# Beetech_Metro_Shield_1_2.net
KiCad netlist of a schematic drawn in Altium Designer
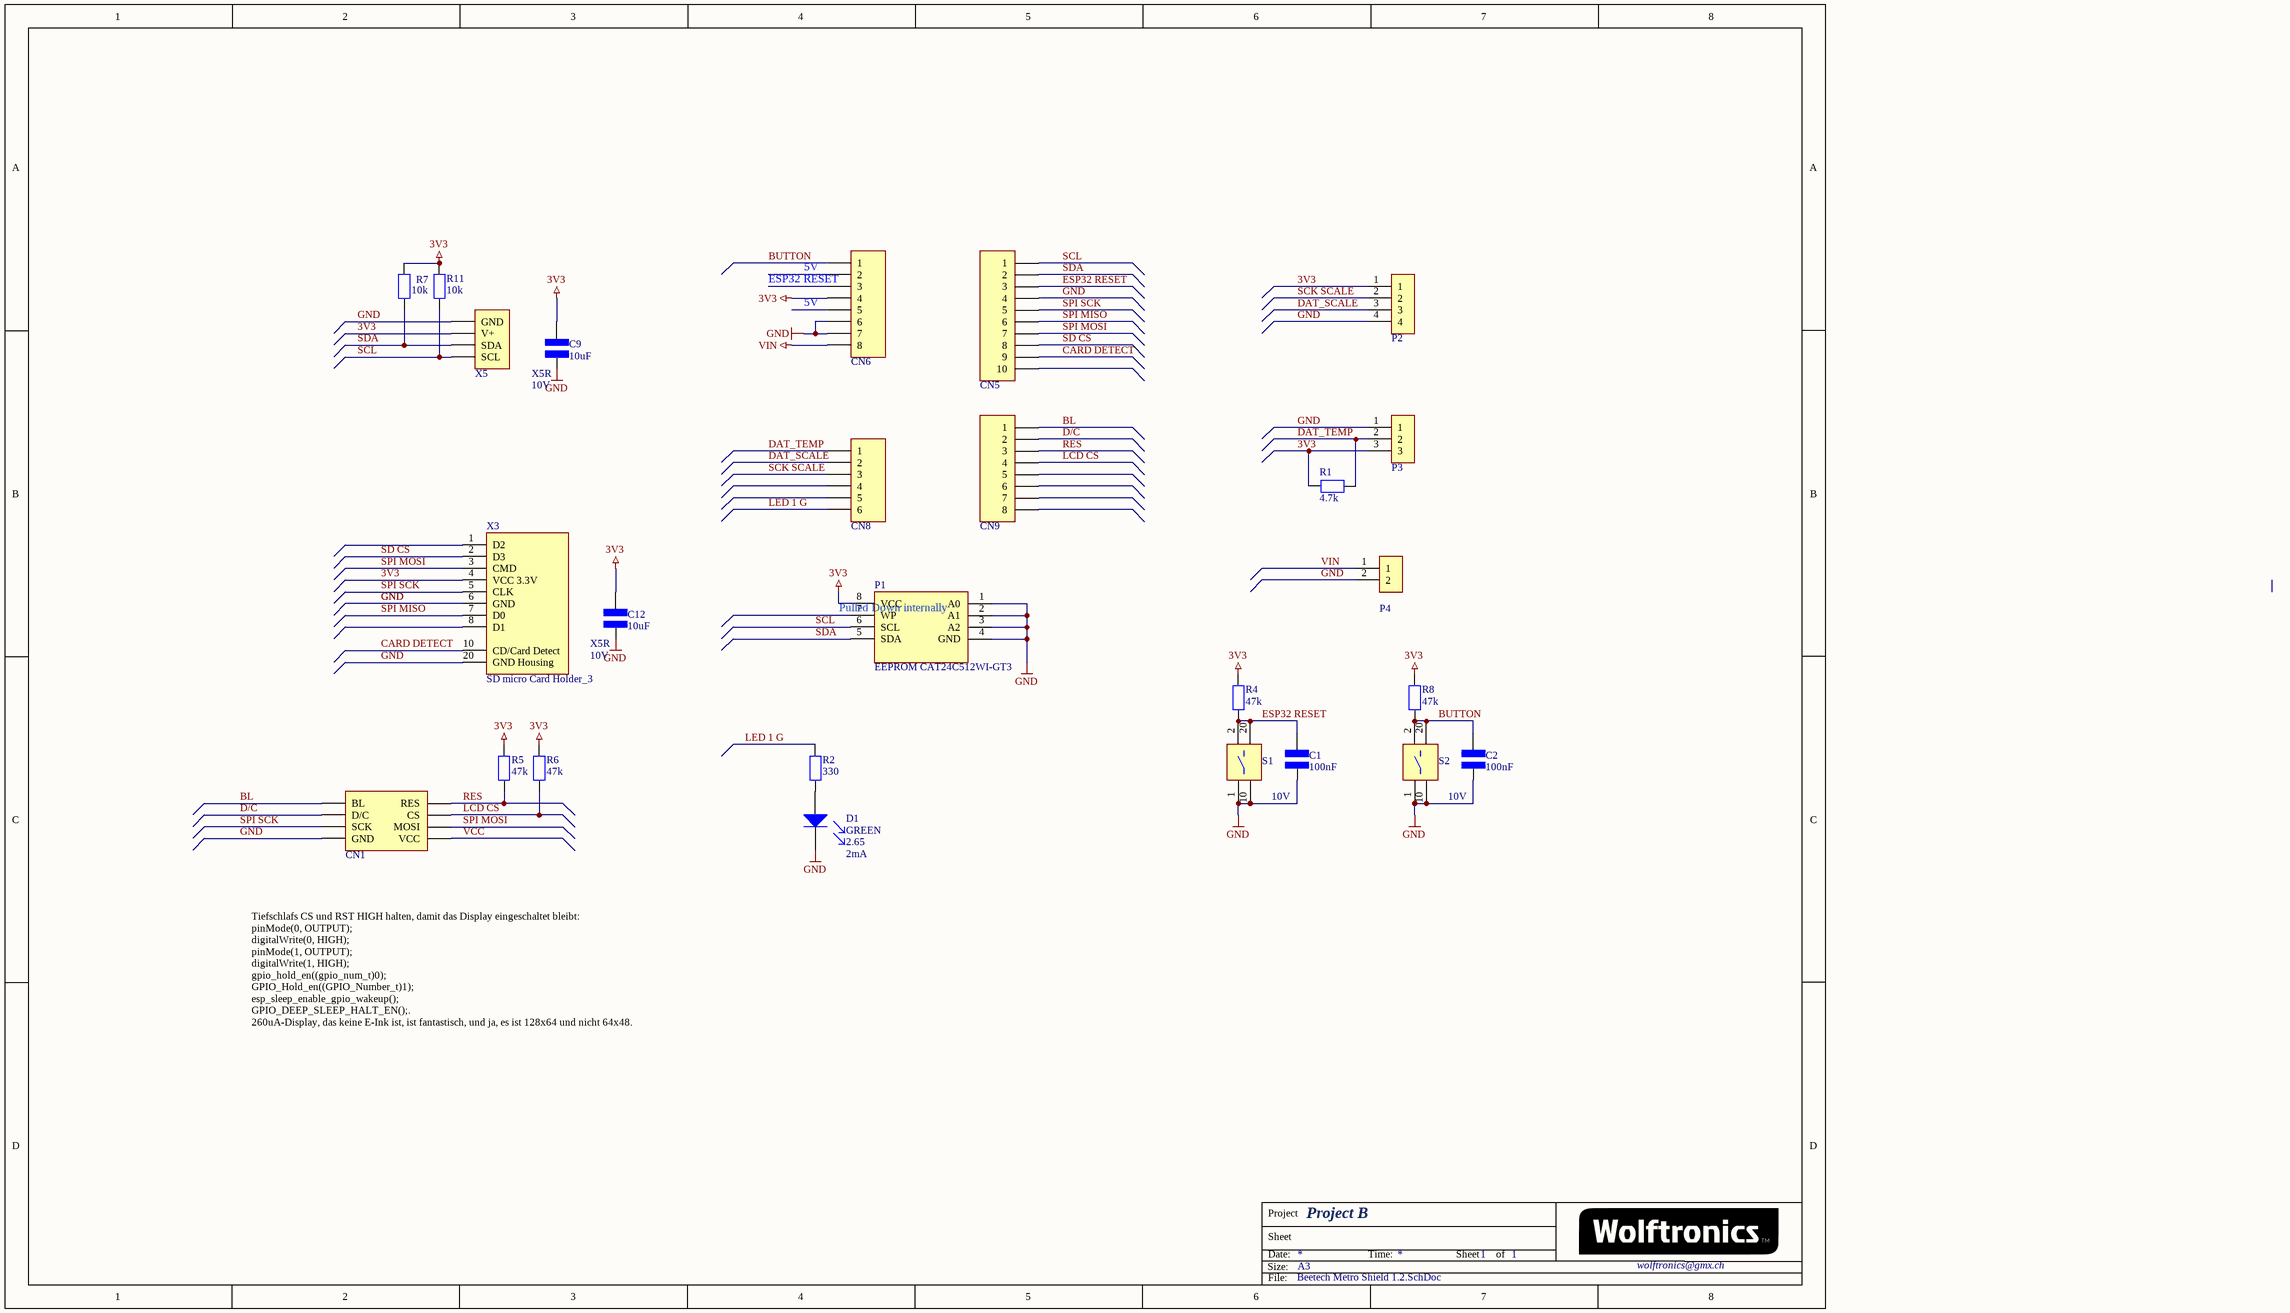
[diagram p0: Beetech Metro Shield 1.2.SchDoc]

(export (version "E")
  (design (tool "Eeschema 10.0.6"))
  (components
    (comp (ref "C1")
      (value "100nF")
      (footprint "CAP 0603 - OUTLINE")
      (description "C CERAMIC SMD")
      (fields (field (name "UMAX") "10V") (field (name "Comment") "100nF 0603"))
      (libsource (lib "Library CAP") (part "100nF 0603"))
    )
    (comp (ref "C2")
      (value "100nF")
      (footprint "CAP 0603 - OUTLINE")
      (description "C CERAMIC SMD")
      (fields (field (name "UMAX") "10V") (field (name "Comment") "100nF 0603"))
      (libsource (lib "Library CAP") (part "100nF 0603"))
    )
    (comp (ref "C9")
      (value "10uF")
      (footprint "CAP 0603 - OUTLINE")
      (description "C CERAMIC SMD")
      (fields
        (field (name "UMAX") "10V")
        (field (name "DIELEKTRIKUM") "X5R")
        (field (name "Comment") "10uF 0603")
      )
      (libsource (lib "Library CAP") (part "10uF 0603"))
    )
    (comp (ref "C12")
      (value "10uF")
      (footprint "CAP 0603 - OUTLINE")
      (description "C CERAMIC SMD")
      (fields
        (field (name "UMAX") "10V")
        (field (name "DIELEKTRIKUM") "X5R")
        (field (name "Comment") "10uF 0603")
      )
      (libsource (lib "Library CAP") (part "10uF 0603"))
    )
    (comp (ref "CN1")
      (value "LCD 1.37 Zoll Matrix")
      (footprint "LCD 1.37 Zoll Matrix LCD-Modul SPI-Schnittstelle Treiber AiP31567 - ST7567")
      (description "1,37 Zoll 1,37 Zoll Matrix LCD-Modul SPI-Schnittstelle AiP31567 Treiber Gleiche wie ST7567")
      (libsource (lib "Library Scematic") (part "LCD 1.37 Zoll Matrix"))
    )
    (comp (ref "CN5")
      (value "10-Pin Stiftleiste 10x1 2.54 Low Profile")
      (footprint "10PIN - III")
      (description "Low Profile 10-Pin Stiftleiste 10x1 2.54 Low Profile")
      (libsource (lib "Library Scematic") (part "10-Pin Stiftleiste 10x1 2.54 Low Profile"))
    )
    (comp (ref "CN6")
      (value "8-Pin Stiftleiste 8x1 2.54 Low Profile")
      (footprint "8 PIN - Stiftleiste")
      (description "Low Profile 8-Pin Stiftleiste 8x1 2.54")
      (libsource (lib "Library Scematic") (part "8-Pin Stiftleiste 8x1 2.54 Low Profile"))
    )
    (comp (ref "CN8")
      (value "6-PiN")
      (footprint "6PIN")
      (description "6-Pin")
      (fields (field (name "PUBLISHER") "Altium Limited"))
      (libsource (lib "Library Scematic") (part "6-PiN"))
    )
    (comp (ref "CN9")
      (value "8-Pin Stiftleiste 8x1 2.54 Low Profile")
      (footprint "8 PIN - Stiftleiste")
      (description "Low Profile 8-Pin Stiftleiste 8x1 2.54")
      (libsource (lib "") (part "8-Pin Stiftleiste 8x1 2.54 Low Profile_1"))
    )
    (comp (ref "D1")
      (value "LED Diode SMD LOW CURRENT")
      (footprint "LED SMD 0603 FOOTPRINT")
      (description "LED Green APT1608LZGCK")
      (fields
        (field (name "COLOR") "GREEN")
        (field (name "FORWARD VOLTAGE") "2.65")
        (field (name "IF") "2mA")
      )
      (libsource (lib "Library DIODE") (part "LED Diode SMD - GREEN - 0603 - 2mA_1"))
    )
    (comp (ref "P1")
      (value "EEPROM CAT24C512WI-GT3")
      (footprint "SO 8Pin")
      (libsource (lib "Library Scematic") (part "EEPROM CAT24C512WI-GT3"))
    )
    (comp (ref "P2")
      (value "4-Pin Right Angle Housing")
      (footprint "4PIN - RND 205-EK254-2.54-04P")
      (description "4-Pin")
      (libsource (lib "Library Scematic") (part "4-Pin Screw Terminal"))
    )
    (comp (ref "P3")
      (value "3-Pin Right Angle Housing")
      (footprint "3PIN - RND 205-EK254-2.54-03P")
      (description "3-Pin")
      (libsource (lib "Library Scematic") (part "3-Pin Screw Terminal"))
    )
    (comp (ref "P4")
      (value "2-Pin Right Angle Housing")
      (footprint "2PIN - RND 205-EK254-2.54-02P")
      (description "2-Pin")
      (libsource (lib "Library Scematic") (part "2-Pin Screw Terminal"))
    )
    (comp (ref "R1")
      (value "4.7k")
      (footprint "RES 0603 FOOTPRINT - OUTLINE")
      (description "R SMD")
      (fields (field (name "Comment") "4.7k Ohm 0603"))
      (libsource (lib "Library RES") (part "4.7k Ohm 0603"))
    )
    (comp (ref "R2")
      (value "330")
      (footprint "RES 0603 FOOTPRINT - OUTLINE")
      (description "R SMD")
      (fields (field (name "Comment") "330 Ohm 0603"))
      (libsource (lib "Library RES") (part "330 Ohm 0603"))
    )
    (comp (ref "R4")
      (value "47k")
      (footprint "RES 0603 FOOTPRINT - OUTLINE")
      (description "R SMD")
      (fields (field (name "Comment") "47k Ohm 0603"))
      (libsource (lib "Library RES") (part "47k Ohm 0603"))
    )
    (comp (ref "R5")
      (value "47k")
      (footprint "RES 0603 FOOTPRINT - OUTLINE")
      (description "R SMD")
      (fields (field (name "Comment") "47k Ohm 0603"))
      (libsource (lib "Library RES") (part "47k Ohm 0603"))
    )
    (comp (ref "R6")
      (value "47k")
      (footprint "RES 0603 FOOTPRINT - OUTLINE")
      (description "R SMD")
      (fields (field (name "Comment") "47k Ohm 0603"))
      (libsource (lib "Library RES") (part "47k Ohm 0603"))
    )
    (comp (ref "R7")
      (value "10k")
      (footprint "RES 0603 FOOTPRINT - OUTLINE")
      (description "R SMD")
      (fields (field (name "Comment") "10k Ohm 0603"))
      (libsource (lib "Library RES") (part "10k Ohm 0603"))
    )
    (comp (ref "R8")
      (value "47k")
      (footprint "RES 0603 FOOTPRINT - OUTLINE")
      (description "R SMD")
      (fields (field (name "Comment") "47k Ohm 0603"))
      (libsource (lib "Library RES") (part "47k Ohm 0603"))
    )
    (comp (ref "R11")
      (value "10k")
      (footprint "RES 0603 FOOTPRINT - OUTLINE")
      (description "R SMD")
      (fields (field (name "Comment") "10k Ohm 0603"))
      (libsource (lib "Library RES") (part "10k Ohm 0603"))
    )
    (comp (ref "S1")
      (value "Taster Print_SMD_2")
      (footprint "Taster Print - SMD - KMR241G LFS")
      (description "Taster")
      (libsource (lib "Library Scematic") (part "Taster Print_SMD_2"))
    )
    (comp (ref "S2")
      (value "Taster Print_SMD_2")
      (footprint "Taster Print - SMD - KMR241G LFS")
      (description "Taster")
      (libsource (lib "Library Scematic") (part "Taster Print_SMD_2"))
    )
    (comp (ref "X3")
      (value "SD micro Card Holder_3")
      (footprint "SD Card Holder - micro - 3 - sd Card inserted")
      (description "SD micro Card  Holder")
      (libsource (lib "Library Scematic") (part "SD micro Card Holder_3"))
    )
    (comp (ref "X5")
      (value "4-Pin")
      (footprint "QWIIC JST CONNECTOR - SMD 4-PIN")
      (description "QWIIC JST CONNECTOR - SMD 4-PIN")
      (libsource (lib "Library Scematic") (part "4-Pin QWIIC JST CONNECTOR - SMD 4_1"))
    )
  )
  (nets
    (net (code "1") (name "/BL") (class "Default")
      (node (ref "CN1") (pin "1") (pinfunction "BL_1") (pintype "passive"))
      (node (ref "CN9") (pin "1") (pinfunction "1_1") (pintype "passive"))
    )
    (net (code "2") (name "/BUTTON") (class "Default")
      (node (ref "C2") (pin "2") (pinfunction "2_2") (pintype "passive"))
      (node (ref "CN6") (pin "1") (pinfunction "1_1") (pintype "passive"))
      (node (ref "R8") (pin "2") (pinfunction "2_2") (pintype "passive"))
      (node (ref "S2") (pin "2") (pinfunction "2_2") (pintype "passive"))
      (node (ref "S2") (pin "20") (pinfunction "20_20") (pintype "passive"))
    )
    (net (code "3") (name "/CARD DETECT") (class "Default")
      (node (ref "CN5") (pin "9") (pinfunction "9_9") (pintype "passive"))
      (node (ref "X3") (pin "10") (pinfunction "CD/Card_Detect_10") (pintype "passive"))
    )
    (net (code "4") (name "/DAT_SCALE") (class "Default")
      (node (ref "CN8") (pin "2") (pinfunction "2_2") (pintype "passive"))
      (node (ref "P2") (pin "3") (pinfunction "3_3") (pintype "passive"))
    )
    (net (code "5") (name "/DAT_TEMP") (class "Default")
      (node (ref "CN8") (pin "1") (pinfunction "1_1") (pintype "passive"))
      (node (ref "P3") (pin "2") (pinfunction "2_2") (pintype "passive"))
      (node (ref "R1") (pin "1") (pinfunction "1_1") (pintype "passive"))
    )
    (net (code "6") (name "/D{slash}C") (class "Default")
      (node (ref "CN1") (pin "3") (pinfunction "D/C_3") (pintype "passive"))
      (node (ref "CN9") (pin "2") (pinfunction "2_2") (pintype "passive"))
    )
    (net (code "7") (name "/ESP32 RESET") (class "Default")
      (node (ref "C1") (pin "2") (pinfunction "2_2") (pintype "passive"))
      (node (ref "CN5") (pin "3") (pinfunction "3_3") (pintype "passive"))
      (node (ref "R4") (pin "2") (pinfunction "2_2") (pintype "passive"))
      (node (ref "S1") (pin "2") (pinfunction "2_2") (pintype "passive"))
      (node (ref "S1") (pin "20") (pinfunction "20_20") (pintype "passive"))
    )
    (net (code "8") (name "/LCD CS") (class "Default")
      (node (ref "CN1") (pin "4") (pinfunction "CS_4") (pintype "passive"))
      (node (ref "CN9") (pin "4") (pinfunction "4_4") (pintype "passive"))
      (node (ref "R6") (pin "1") (pinfunction "1_1") (pintype "passive"))
    )
    (net (code "9") (name "/LED 1 G") (class "Default")
      (node (ref "CN8") (pin "6") (pinfunction "6_6") (pintype "passive"))
      (node (ref "R2") (pin "2") (pinfunction "2_2") (pintype "passive"))
    )
    (net (code "10") (name "/RES") (class "Default")
      (node (ref "CN1") (pin "2") (pinfunction "RES_2") (pintype "passive"))
      (node (ref "CN9") (pin "3") (pinfunction "3_3") (pintype "passive"))
      (node (ref "R5") (pin "1") (pinfunction "1_1") (pintype "passive"))
    )
    (net (code "11") (name "/SCK SCALE") (class "Default")
      (node (ref "CN8") (pin "3") (pinfunction "3_3") (pintype "passive"))
      (node (ref "P2") (pin "2") (pinfunction "2_2") (pintype "passive"))
    )
    (net (code "12") (name "/SCL") (class "Default")
      (node (ref "CN5") (pin "1") (pinfunction "1_1") (pintype "passive"))
      (node (ref "P1") (pin "6") (pinfunction "SCL_6") (pintype "passive"))
      (node (ref "R11") (pin "1") (pinfunction "1_1") (pintype "passive"))
      (node (ref "X5") (pin "1") (pinfunction "SCL_1") (pintype "passive"))
    )
    (net (code "13") (name "/SD CS") (class "Default")
      (node (ref "CN5") (pin "8") (pinfunction "8_8") (pintype "passive"))
      (node (ref "X3") (pin "2") (pinfunction "D3_2") (pintype "passive"))
    )
    (net (code "14") (name "/SDA") (class "Default")
      (node (ref "CN5") (pin "2") (pinfunction "2_2") (pintype "passive"))
      (node (ref "P1") (pin "5") (pinfunction "SDA_5") (pintype "passive"))
      (node (ref "R7") (pin "1") (pinfunction "1_1") (pintype "passive"))
      (node (ref "X5") (pin "2") (pinfunction "SDA_2") (pintype "passive"))
    )
    (net (code "15") (name "/SPI MISO") (class "Default")
      (node (ref "CN5") (pin "6") (pinfunction "6_6") (pintype "passive"))
      (node (ref "X3") (pin "7") (pinfunction "D0_7") (pintype "passive"))
    )
    (net (code "16") (name "/SPI MOSI") (class "Default")
      (node (ref "CN1") (pin "6") (pinfunction "MOSI_6") (pintype "passive"))
      (node (ref "CN5") (pin "7") (pinfunction "7_7") (pintype "passive"))
      (node (ref "X3") (pin "3") (pinfunction "CMD_3") (pintype "passive"))
    )
    (net (code "17") (name "/SPI SCK") (class "Default")
      (node (ref "CN1") (pin "5") (pinfunction "SCK_5") (pintype "passive"))
      (node (ref "CN5") (pin "5") (pinfunction "5_5") (pintype "passive"))
      (node (ref "X3") (pin "5") (pinfunction "CLK_5") (pintype "passive"))
    )
    (net (code "18") (name "/VCC") (class "Default")
      (node (ref "CN1") (pin "8") (pinfunction "VCC_8") (pintype "passive"))
    )
    (net (code "19") (name "3V3") (class "Default")
      (node (ref "C12") (pin "2") (pinfunction "2_2") (pintype "passive"))
      (node (ref "C9") (pin "2") (pinfunction "2_2") (pintype "passive"))
      (node (ref "CN6") (pin "4") (pinfunction "4_4") (pintype "passive"))
      (node (ref "P1") (pin "8") (pinfunction "VCC_8") (pintype "passive"))
      (node (ref "P2") (pin "1") (pinfunction "1_1") (pintype "passive"))
      (node (ref "P3") (pin "3") (pinfunction "3_3") (pintype "passive"))
      (node (ref "R1") (pin "2") (pinfunction "2_2") (pintype "passive"))
      (node (ref "R11") (pin "2") (pinfunction "2_2") (pintype "passive"))
      (node (ref "R4") (pin "1") (pinfunction "1_1") (pintype "passive"))
      (node (ref "R5") (pin "2") (pinfunction "2_2") (pintype "passive"))
      (node (ref "R6") (pin "2") (pinfunction "2_2") (pintype "passive"))
      (node (ref "R7") (pin "2") (pinfunction "2_2") (pintype "passive"))
      (node (ref "R8") (pin "1") (pinfunction "1_1") (pintype "passive"))
      (node (ref "X3") (pin "4") (pinfunction "VCC_3.3V_4") (pintype "passive"))
      (node (ref "X5") (pin "3") (pinfunction "V+_3") (pintype "passive"))
    )
    (net (code "20") (name "GND") (class "Default")
      (node (ref "C1") (pin "1") (pinfunction "1_1") (pintype "passive"))
      (node (ref "C12") (pin "1") (pinfunction "1_1") (pintype "passive"))
      (node (ref "C2") (pin "1") (pinfunction "1_1") (pintype "passive"))
      (node (ref "C9") (pin "1") (pinfunction "1_1") (pintype "passive"))
      (node (ref "CN1") (pin "7") (pinfunction "GND_7") (pintype "passive"))
      (node (ref "CN5") (pin "4") (pinfunction "4_4") (pintype "passive"))
      (node (ref "CN6") (pin "6") (pinfunction "6_6") (pintype "passive"))
      (node (ref "CN6") (pin "7") (pinfunction "7_7") (pintype "passive"))
      (node (ref "D1") (pin "2") (pinfunction "K_2") (pintype "passive"))
      (node (ref "P1") (pin "1") (pinfunction "A0_1") (pintype "passive"))
      (node (ref "P1") (pin "2") (pinfunction "A1_2") (pintype "passive"))
      (node (ref "P1") (pin "3") (pinfunction "A2_3") (pintype "passive"))
      (node (ref "P1") (pin "4") (pinfunction "GND_4") (pintype "passive"))
      (node (ref "P2") (pin "4") (pinfunction "4_4") (pintype "passive"))
      (node (ref "P3") (pin "1") (pinfunction "1_1") (pintype "passive"))
      (node (ref "P4") (pin "2") (pinfunction "2_2") (pintype "passive"))
      (node (ref "S1") (pin "1") (pinfunction "1_1") (pintype "passive"))
      (node (ref "S1") (pin "10") (pinfunction "10_10") (pintype "passive"))
      (node (ref "S2") (pin "1") (pinfunction "1_1") (pintype "passive"))
      (node (ref "S2") (pin "10") (pinfunction "10_10") (pintype "passive"))
      (node (ref "X3") (pin "20") (pinfunction "GND_Housing_20") (pintype "passive"))
      (node (ref "X3") (pin "6") (pinfunction "GND_6") (pintype "passive"))
      (node (ref "X5") (pin "4") (pinfunction "GND_4") (pintype "passive"))
    )
    (net (code "21") (name "Net-(D1-A)") (class "Default")
      (node (ref "D1") (pin "1") (pinfunction "A_1") (pintype "passive"))
      (node (ref "R2") (pin "1") (pinfunction "1_1") (pintype "passive"))
    )
    (net (code "22") (name "VIN") (class "Default")
      (node (ref "CN6") (pin "8") (pinfunction "8_8") (pintype "passive"))
      (node (ref "P4") (pin "1") (pinfunction "1_1") (pintype "passive"))
    )
    (net (code "23") (name "unconnected-(CN5-Pad10)") (class "Default")
      (node (ref "CN5") (pin "10") (pinfunction "10_10") (pintype "passive"))
    )
    (net (code "24") (name "unconnected-(CN6-Pad2)") (class "Default")
      (node (ref "CN6") (pin "2") (pinfunction "2_2") (pintype "passive"))
    )
    (net (code "25") (name "unconnected-(CN6-Pad3)") (class "Default")
      (node (ref "CN6") (pin "3") (pinfunction "3_3") (pintype "passive"))
    )
    (net (code "26") (name "unconnected-(CN6-Pad5)") (class "Default")
      (node (ref "CN6") (pin "5") (pinfunction "5_5") (pintype "passive"))
    )
    (net (code "27") (name "unconnected-(CN8-Pad4)") (class "Default")
      (node (ref "CN8") (pin "4") (pinfunction "4_4") (pintype "passive"))
    )
    (net (code "28") (name "unconnected-(CN8-Pad5)") (class "Default")
      (node (ref "CN8") (pin "5") (pinfunction "5_5") (pintype "passive"))
    )
    (net (code "29") (name "unconnected-(CN9-Pad5)") (class "Default")
      (node (ref "CN9") (pin "5") (pinfunction "5_5") (pintype "passive"))
    )
    (net (code "30") (name "unconnected-(CN9-Pad6)") (class "Default")
      (node (ref "CN9") (pin "6") (pinfunction "6_6") (pintype "passive"))
    )
    (net (code "31") (name "unconnected-(CN9-Pad7)") (class "Default")
      (node (ref "CN9") (pin "7") (pinfunction "7_7") (pintype "passive"))
    )
    (net (code "32") (name "unconnected-(CN9-Pad8)") (class "Default")
      (node (ref "CN9") (pin "8") (pinfunction "8_8") (pintype "passive"))
    )
    (net (code "33") (name "unconnected-(P1-WP-Pad7)") (class "Default")
      (node (ref "P1") (pin "7") (pinfunction "WP_7") (pintype "passive"))
    )
    (net (code "34") (name "unconnected-(X3-D1-Pad8)") (class "Default")
      (node (ref "X3") (pin "8") (pinfunction "D1_8") (pintype "passive"))
    )
    (net (code "35") (name "unconnected-(X3-D2-Pad1)") (class "Default")
      (node (ref "X3") (pin "1") (pinfunction "D2_1") (pintype "passive"))
    )
  )
)
